# RHA2132_headstage.net
KiCad netlist of a schematic drawn in EAGLE
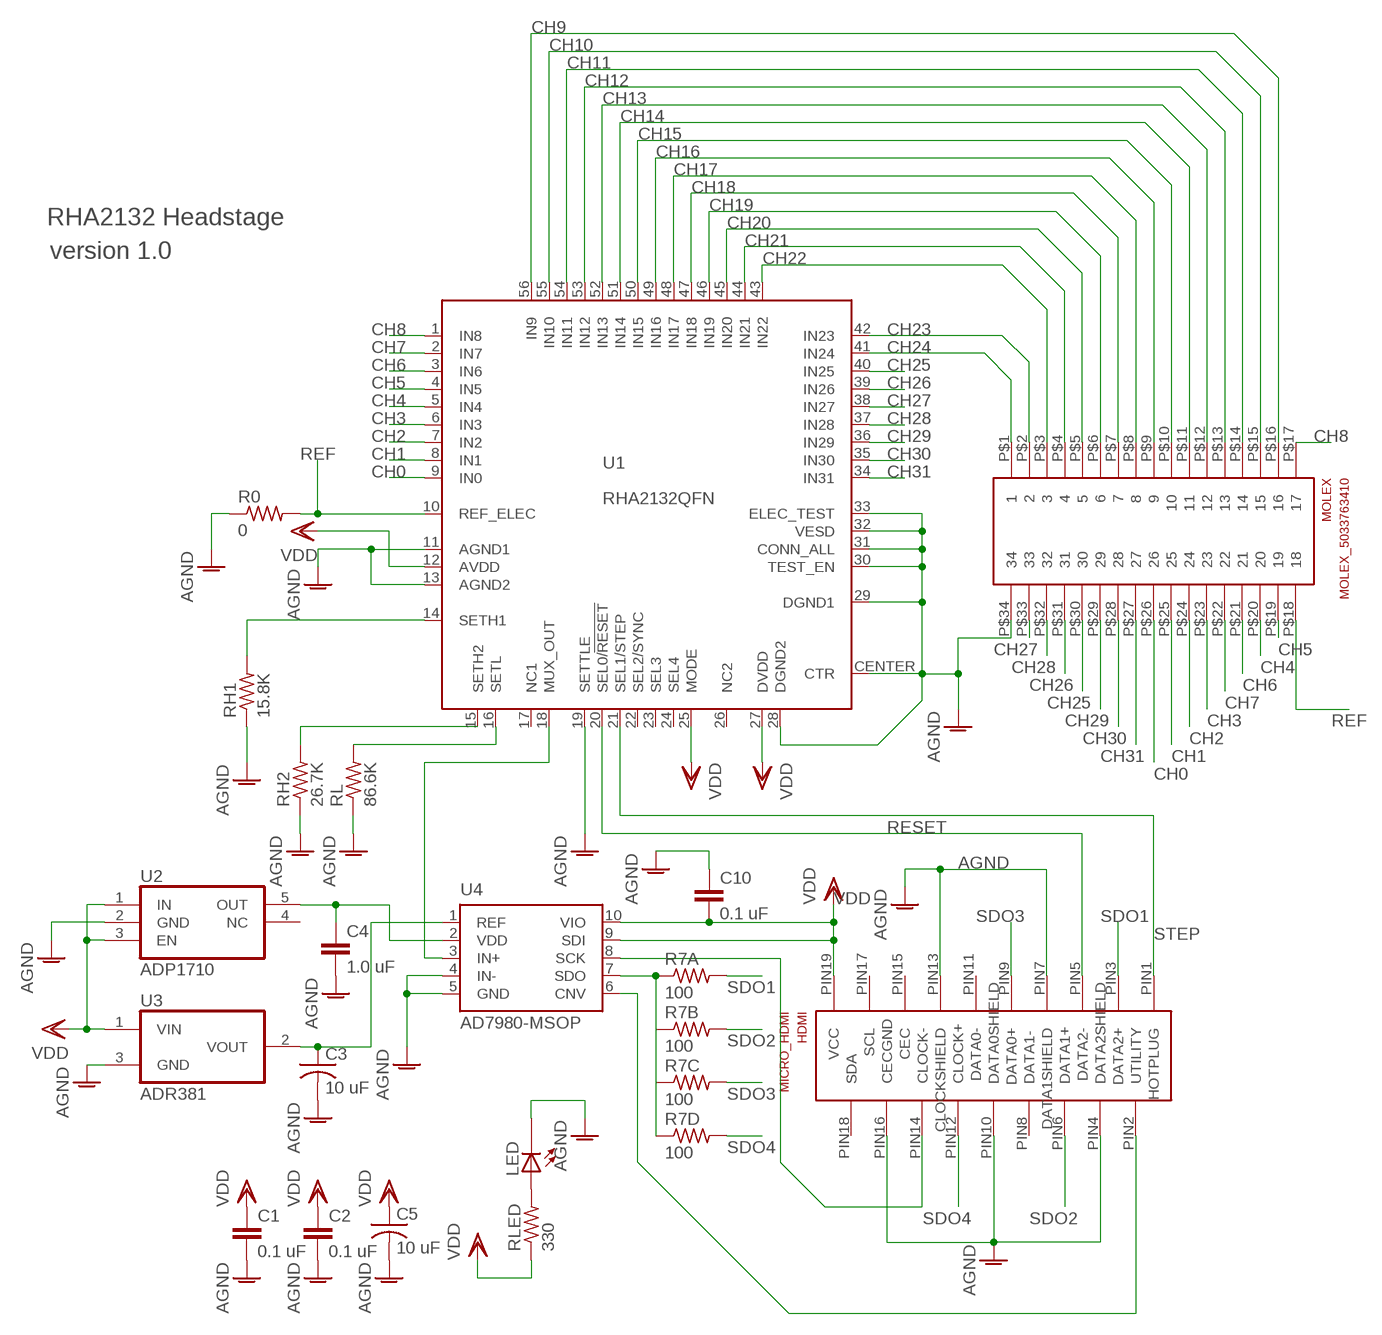
[diagram p0: schematic, sheet 1]

(export (version "E")
  (design (tool "Eeschema 10.0.6"))
  (components
    (comp (ref "C1")
      (value "0.1 uF")
      (footprint "eagle-import:C0402")
      (libsource (lib "eagle-import") (part "C-EUC0402"))
    )
    (comp (ref "C2")
      (value "0.1 uF")
      (footprint "eagle-import:C0402")
      (libsource (lib "eagle-import") (part "C-EUC0402"))
    )
    (comp (ref "C3")
      (value "10 uF")
      (footprint "eagle-import:C0603")
      (libsource (lib "eagle-import") (part "C-USC0603"))
    )
    (comp (ref "C4")
      (value "1.0 uF")
      (footprint "eagle-import:C0402")
      (libsource (lib "eagle-import") (part "C-EUC0402"))
    )
    (comp (ref "C5")
      (value "10 uF")
      (footprint "eagle-import:C0603")
      (libsource (lib "eagle-import") (part "C-USC0603"))
    )
    (comp (ref "C10")
      (value "0.1 uF")
      (footprint "eagle-import:C0402")
      (libsource (lib "eagle-import") (part "C-EUC0402"))
    )
    (comp (ref "HDMI")
      (value "MICRO_HDMI")
      (footprint "eagle-import:MICRO_HDMI")
      (libsource (lib "eagle-import") (part "MICRO_HDMI"))
    )
    (comp (ref "LED")
      (value "LUXEON_REBEL")
      (footprint "eagle-import:LUXEON_REBEL")
      (libsource (lib "eagle-import") (part "LUXEON_REBEL"))
    )
    (comp (ref "MOLEX")
      (value "MOLEX_5033763410")
      (footprint "eagle-import:MOLEX_5033763410")
      (libsource (lib "eagle-import") (part "MOLEX_5033763410"))
    )
    (comp (ref "R0")
      (value "0")
      (footprint "eagle-import:R0603")
      (libsource (lib "eagle-import") (part "R-US_R0603"))
    )
    (comp (ref "R7A")
      (value "100")
      (footprint "eagle-import:R0402")
      (libsource (lib "eagle-import") (part "R-US_R0402"))
    )
    (comp (ref "R7B")
      (value "100")
      (footprint "eagle-import:R0402")
      (libsource (lib "eagle-import") (part "R-US_R0402"))
    )
    (comp (ref "R7C")
      (value "100")
      (footprint "eagle-import:R0402")
      (libsource (lib "eagle-import") (part "R-US_R0402"))
    )
    (comp (ref "R7D")
      (value "100")
      (footprint "eagle-import:R0402")
      (libsource (lib "eagle-import") (part "R-US_R0402"))
    )
    (comp (ref "RH1")
      (value "15.8K")
      (footprint "eagle-import:R0402")
      (libsource (lib "eagle-import") (part "R-US_R0402"))
    )
    (comp (ref "RH2")
      (value "26.7K")
      (footprint "eagle-import:R0402")
      (libsource (lib "eagle-import") (part "R-US_R0402"))
    )
    (comp (ref "RL")
      (value "86.6K")
      (footprint "eagle-import:R0402")
      (libsource (lib "eagle-import") (part "R-US_R0402"))
    )
    (comp (ref "RLED")
      (value "330")
      (footprint "eagle-import:R0402")
      (libsource (lib "eagle-import") (part "R-US_R0402"))
    )
    (comp (ref "U1")
      (value "RHA2132QFN")
      (footprint "eagle-import:QFN56_8_X_8")
      (libsource (lib "eagle-import") (part "RHA2132QFN"))
    )
    (comp (ref "U2")
      (value "ADP1710")
      (footprint "eagle-import:TSOT-23-5")
      (libsource (lib "eagle-import") (part "ADP1710"))
    )
    (comp (ref "U3")
      (value "ADR381")
      (footprint "eagle-import:SOT23")
      (libsource (lib "eagle-import") (part "ADR381"))
    )
    (comp (ref "U4")
      (value "AD7980-MSOP")
      (footprint "eagle-import:MSOP-10")
      (libsource (lib "eagle-import") (part "AD7980-MSOP"))
    )
  )
  (nets
    (net (code "1") (name "/CH0") (class "Default")
      (node (ref "MOLEX") (pin "P$26") (pinfunction "26_P$26") (pintype "bidirectional"))
      (node (ref "U1") (pin "9") (pinfunction "IN0_9") (pintype "input"))
    )
    (net (code "2") (name "/CH1") (class "Default")
      (node (ref "MOLEX") (pin "P$25") (pinfunction "25_P$25") (pintype "bidirectional"))
      (node (ref "U1") (pin "8") (pinfunction "IN1_8") (pintype "input"))
    )
    (net (code "3") (name "/CH2") (class "Default")
      (node (ref "MOLEX") (pin "P$24") (pinfunction "24_P$24") (pintype "bidirectional"))
      (node (ref "U1") (pin "7") (pinfunction "IN2_7") (pintype "input"))
    )
    (net (code "4") (name "/CH3") (class "Default")
      (node (ref "MOLEX") (pin "P$23") (pinfunction "23_P$23") (pintype "bidirectional"))
      (node (ref "U1") (pin "6") (pinfunction "IN3_6") (pintype "input"))
    )
    (net (code "5") (name "/CH4") (class "Default")
      (node (ref "MOLEX") (pin "P$20") (pinfunction "20_P$20") (pintype "bidirectional"))
      (node (ref "U1") (pin "5") (pinfunction "IN4_5") (pintype "input"))
    )
    (net (code "6") (name "/CH5") (class "Default")
      (node (ref "MOLEX") (pin "P$19") (pinfunction "19_P$19") (pintype "bidirectional"))
      (node (ref "U1") (pin "4") (pinfunction "IN5_4") (pintype "input"))
    )
    (net (code "7") (name "/CH6") (class "Default")
      (node (ref "MOLEX") (pin "P$21") (pinfunction "21_P$21") (pintype "bidirectional"))
      (node (ref "U1") (pin "3") (pinfunction "IN6_3") (pintype "input"))
    )
    (net (code "8") (name "/CH7") (class "Default")
      (node (ref "MOLEX") (pin "P$22") (pinfunction "22_P$22") (pintype "bidirectional"))
      (node (ref "U1") (pin "2") (pinfunction "IN7_2") (pintype "input"))
    )
    (net (code "9") (name "/CH8") (class "Default")
      (node (ref "MOLEX") (pin "P$17") (pinfunction "17_P$17") (pintype "bidirectional"))
      (node (ref "U1") (pin "1") (pinfunction "IN8_1") (pintype "input"))
    )
    (net (code "10") (name "/CH9") (class "Default")
      (node (ref "MOLEX") (pin "P$16") (pinfunction "16_P$16") (pintype "bidirectional"))
      (node (ref "U1") (pin "56") (pinfunction "IN9_56") (pintype "input"))
    )
    (net (code "11") (name "/CH10") (class "Default")
      (node (ref "MOLEX") (pin "P$15") (pinfunction "15_P$15") (pintype "bidirectional"))
      (node (ref "U1") (pin "55") (pinfunction "IN10_55") (pintype "input"))
    )
    (net (code "12") (name "/CH11") (class "Default")
      (node (ref "MOLEX") (pin "P$14") (pinfunction "14_P$14") (pintype "bidirectional"))
      (node (ref "U1") (pin "54") (pinfunction "IN11_54") (pintype "input"))
    )
    (net (code "13") (name "/CH12") (class "Default")
      (node (ref "MOLEX") (pin "P$13") (pinfunction "13_P$13") (pintype "bidirectional"))
      (node (ref "U1") (pin "53") (pinfunction "IN12_53") (pintype "input"))
    )
    (net (code "14") (name "/CH13") (class "Default")
      (node (ref "MOLEX") (pin "P$12") (pinfunction "12_P$12") (pintype "bidirectional"))
      (node (ref "U1") (pin "52") (pinfunction "IN13_52") (pintype "input"))
    )
    (net (code "15") (name "/CH14") (class "Default")
      (node (ref "MOLEX") (pin "P$11") (pinfunction "11_P$11") (pintype "bidirectional"))
      (node (ref "U1") (pin "51") (pinfunction "IN14_51") (pintype "input"))
    )
    (net (code "16") (name "/CH15") (class "Default")
      (node (ref "MOLEX") (pin "P$10") (pinfunction "10_P$10") (pintype "bidirectional"))
      (node (ref "U1") (pin "50") (pinfunction "IN15_50") (pintype "input"))
    )
    (net (code "17") (name "/CH16") (class "Default")
      (node (ref "MOLEX") (pin "P$9") (pinfunction "9_P$9") (pintype "bidirectional"))
      (node (ref "U1") (pin "49") (pinfunction "IN16_49") (pintype "input"))
    )
    (net (code "18") (name "/CH17") (class "Default")
      (node (ref "MOLEX") (pin "P$8") (pinfunction "8_P$8") (pintype "bidirectional"))
      (node (ref "U1") (pin "48") (pinfunction "IN17_48") (pintype "input"))
    )
    (net (code "19") (name "/CH18") (class "Default")
      (node (ref "MOLEX") (pin "P$7") (pinfunction "7_P$7") (pintype "bidirectional"))
      (node (ref "U1") (pin "47") (pinfunction "IN18_47") (pintype "input"))
    )
    (net (code "20") (name "/CH19") (class "Default")
      (node (ref "MOLEX") (pin "P$6") (pinfunction "6_P$6") (pintype "bidirectional"))
      (node (ref "U1") (pin "46") (pinfunction "IN19_46") (pintype "input"))
    )
    (net (code "21") (name "/CH20") (class "Default")
      (node (ref "MOLEX") (pin "P$5") (pinfunction "5_P$5") (pintype "bidirectional"))
      (node (ref "U1") (pin "45") (pinfunction "IN20_45") (pintype "input"))
    )
    (net (code "22") (name "/CH21") (class "Default")
      (node (ref "MOLEX") (pin "P$4") (pinfunction "4_P$4") (pintype "bidirectional"))
      (node (ref "U1") (pin "44") (pinfunction "IN21_44") (pintype "input"))
    )
    (net (code "23") (name "/CH22") (class "Default")
      (node (ref "MOLEX") (pin "P$3") (pinfunction "3_P$3") (pintype "bidirectional"))
      (node (ref "U1") (pin "43") (pinfunction "IN22_43") (pintype "input"))
    )
    (net (code "24") (name "/CH23") (class "Default")
      (node (ref "MOLEX") (pin "P$2") (pinfunction "2_P$2") (pintype "bidirectional"))
      (node (ref "U1") (pin "42") (pinfunction "IN23_42") (pintype "input"))
    )
    (net (code "25") (name "/CH24") (class "Default")
      (node (ref "MOLEX") (pin "P$1") (pinfunction "1_P$1") (pintype "bidirectional"))
      (node (ref "U1") (pin "41") (pinfunction "IN24_41") (pintype "input"))
    )
    (net (code "26") (name "/CH25") (class "Default")
      (node (ref "MOLEX") (pin "P$30") (pinfunction "30_P$30") (pintype "bidirectional"))
      (node (ref "U1") (pin "40") (pinfunction "IN25_40") (pintype "input"))
    )
    (net (code "27") (name "/CH26") (class "Default")
      (node (ref "MOLEX") (pin "P$31") (pinfunction "31_P$31") (pintype "bidirectional"))
      (node (ref "U1") (pin "39") (pinfunction "IN26_39") (pintype "input"))
    )
    (net (code "28") (name "/CH27") (class "Default")
      (node (ref "MOLEX") (pin "P$33") (pinfunction "33_P$33") (pintype "bidirectional"))
      (node (ref "U1") (pin "38") (pinfunction "IN27_38") (pintype "input"))
    )
    (net (code "29") (name "/CH28") (class "Default")
      (node (ref "MOLEX") (pin "P$32") (pinfunction "32_P$32") (pintype "bidirectional"))
      (node (ref "U1") (pin "37") (pinfunction "IN28_37") (pintype "input"))
    )
    (net (code "30") (name "/CH29") (class "Default")
      (node (ref "MOLEX") (pin "P$29") (pinfunction "29_P$29") (pintype "bidirectional"))
      (node (ref "U1") (pin "36") (pinfunction "IN29_36") (pintype "input"))
    )
    (net (code "31") (name "/CH30") (class "Default")
      (node (ref "MOLEX") (pin "P$28") (pinfunction "28_P$28") (pintype "bidirectional"))
      (node (ref "U1") (pin "35") (pinfunction "IN30_35") (pintype "input"))
    )
    (net (code "32") (name "/CH31") (class "Default")
      (node (ref "MOLEX") (pin "P$27") (pinfunction "27_P$27") (pintype "bidirectional"))
      (node (ref "U1") (pin "34") (pinfunction "IN31_34") (pintype "input"))
    )
    (net (code "33") (name "/REF") (class "Default")
      (node (ref "MOLEX") (pin "P$18") (pinfunction "18_P$18") (pintype "bidirectional"))
      (node (ref "R0") (pin "2") (pinfunction "2_2") (pintype "passive"))
      (node (ref "U1") (pin "10") (pinfunction "REF_ELEC_10") (pintype "input"))
    )
    (net (code "34") (name "/RESET") (class "Default")
      (node (ref "HDMI") (pin "PIN5") (pinfunction "DATA2-_PIN5") (pintype "bidirectional"))
      (node (ref "U1") (pin "20") (pinfunction "SEL0/~{RESET}_20") (pintype "input"))
    )
    (net (code "35") (name "/SDO1") (class "Default")
      (node (ref "HDMI") (pin "PIN3") (pinfunction "DATA2+_PIN3") (pintype "bidirectional"))
      (node (ref "R7A") (pin "2") (pinfunction "2_2") (pintype "passive"))
    )
    (net (code "36") (name "/SDO2") (class "Default")
      (node (ref "HDMI") (pin "PIN6") (pinfunction "DATA1+_PIN6") (pintype "bidirectional"))
      (node (ref "R7B") (pin "2") (pinfunction "2_2") (pintype "passive"))
    )
    (net (code "37") (name "/SDO3") (class "Default")
      (node (ref "HDMI") (pin "PIN9") (pinfunction "DATA0+_PIN9") (pintype "bidirectional"))
      (node (ref "R7C") (pin "2") (pinfunction "2_2") (pintype "passive"))
    )
    (net (code "38") (name "/SDO4") (class "Default")
      (node (ref "HDMI") (pin "PIN12") (pinfunction "CLOCK+_PIN12") (pintype "bidirectional"))
      (node (ref "R7D") (pin "2") (pinfunction "2_2") (pintype "passive"))
    )
    (net (code "39") (name "/STEP") (class "Default")
      (node (ref "HDMI") (pin "PIN1") (pinfunction "HOTPLUG_PIN1") (pintype "bidirectional"))
      (node (ref "U1") (pin "21") (pinfunction "SEL1/STEP_21") (pintype "input"))
    )
    (net (code "40") (name "AGND") (class "Default")
      (node (ref "C1") (pin "2") (pinfunction "2_2") (pintype "passive"))
      (node (ref "C10") (pin "1") (pinfunction "1_1") (pintype "passive"))
      (node (ref "C2") (pin "2") (pinfunction "2_2") (pintype "passive"))
      (node (ref "C3") (pin "2") (pinfunction "2_2") (pintype "passive"))
      (node (ref "C4") (pin "2") (pinfunction "2_2") (pintype "passive"))
      (node (ref "C5") (pin "2") (pinfunction "2_2") (pintype "passive"))
      (node (ref "HDMI") (pin "PIN10") (pinfunction "DATA0SHIELD_PIN10") (pintype "bidirectional"))
      (node (ref "HDMI") (pin "PIN13") (pinfunction "CLOCKSHIELD_PIN13") (pintype "bidirectional"))
      (node (ref "HDMI") (pin "PIN16") (pinfunction "CECGND_PIN16") (pintype "bidirectional"))
      (node (ref "HDMI") (pin "PIN4") (pinfunction "DATA2SHIELD_PIN4") (pintype "bidirectional"))
      (node (ref "HDMI") (pin "PIN7") (pinfunction "DATA1SHIELD_PIN7") (pintype "bidirectional"))
      (node (ref "LED") (pin "C") (pinfunction "C_C") (pintype "passive"))
      (node (ref "MOLEX") (pin "P$34") (pinfunction "34_P$34") (pintype "bidirectional"))
      (node (ref "R0") (pin "1") (pinfunction "1_1") (pintype "passive"))
      (node (ref "RH1") (pin "1") (pinfunction "1_1") (pintype "passive"))
      (node (ref "RH2") (pin "1") (pinfunction "1_1") (pintype "passive"))
      (node (ref "RL") (pin "1") (pinfunction "1_1") (pintype "passive"))
      (node (ref "U1") (pin "11") (pinfunction "AGND1_11") (pintype "power_in"))
      (node (ref "U1") (pin "13") (pinfunction "AGND2_13") (pintype "power_in"))
      (node (ref "U1") (pin "19") (pinfunction "SETTLE_19") (pintype "input"))
      (node (ref "U1") (pin "28") (pinfunction "DGND2_28") (pintype "power_in"))
      (node (ref "U1") (pin "29") (pinfunction "DGND1_29") (pintype "power_in"))
      (node (ref "U1") (pin "30") (pinfunction "TEST_EN_30") (pintype "input"))
      (node (ref "U1") (pin "31") (pinfunction "CONN_ALL_31") (pintype "input"))
      (node (ref "U1") (pin "32") (pinfunction "VESD_32") (pintype "power_in"))
      (node (ref "U1") (pin "33") (pinfunction "ELEC_TEST_33") (pintype "input"))
      (node (ref "U1") (pin "CENTER") (pinfunction "CTR_CENTER") (pintype "power_in"))
      (node (ref "U2") (pin "2") (pinfunction "GND_2") (pintype "power_in"))
      (node (ref "U3") (pin "3") (pinfunction "GND_3") (pintype "power_in"))
      (node (ref "U4") (pin "4") (pinfunction "IN-_4") (pintype "input"))
      (node (ref "U4") (pin "5") (pinfunction "GND_5") (pintype "power_in"))
    )
    (net (code "41") (name "Net-(HDMI-CLOCK-)") (class "Default")
      (node (ref "HDMI") (pin "PIN14") (pinfunction "CLOCK-_PIN14") (pintype "bidirectional"))
      (node (ref "U4") (pin "8") (pinfunction "SCK_8") (pintype "input"))
    )
    (net (code "42") (name "Net-(HDMI-UTILITY)") (class "Default")
      (node (ref "HDMI") (pin "PIN2") (pinfunction "UTILITY_PIN2") (pintype "bidirectional"))
      (node (ref "U4") (pin "6") (pinfunction "CNV_6") (pintype "input"))
    )
    (net (code "43") (name "Net-(LED-PadA)") (class "Default")
      (node (ref "LED") (pin "A") (pinfunction "A_A") (pintype "passive"))
      (node (ref "RLED") (pin "2") (pinfunction "2_2") (pintype "passive"))
    )
    (net (code "44") (name "Net-(U1-MUX_OUT)") (class "Default")
      (node (ref "U1") (pin "18") (pinfunction "MUX_OUT_18") (pintype "tri_state"))
      (node (ref "U4") (pin "3") (pinfunction "IN+_3") (pintype "input"))
    )
    (net (code "45") (name "Net-(U1-SETH1)") (class "Default")
      (node (ref "RH1") (pin "2") (pinfunction "2_2") (pintype "passive"))
      (node (ref "U1") (pin "14") (pinfunction "SETH1_14") (pintype "passive"))
    )
    (net (code "46") (name "Net-(U1-SETH2)") (class "Default")
      (node (ref "RH2") (pin "2") (pinfunction "2_2") (pintype "passive"))
      (node (ref "U1") (pin "15") (pinfunction "SETH2_15") (pintype "passive"))
    )
    (net (code "47") (name "Net-(U1-SETL)") (class "Default")
      (node (ref "RL") (pin "2") (pinfunction "2_2") (pintype "passive"))
      (node (ref "U1") (pin "16") (pinfunction "SETL_16") (pintype "passive"))
    )
    (net (code "48") (name "Net-(U2-OUT)") (class "Default")
      (node (ref "C4") (pin "1") (pinfunction "1_1") (pintype "passive"))
      (node (ref "U2") (pin "5") (pinfunction "OUT_5") (pintype "power_in"))
      (node (ref "U4") (pin "2") (pinfunction "VDD_2") (pintype "power_in"))
    )
    (net (code "49") (name "Net-(U3-VOUT)") (class "Default")
      (node (ref "C3") (pin "1") (pinfunction "1_1") (pintype "passive"))
      (node (ref "U3") (pin "2") (pinfunction "VOUT_2") (pintype "power_in"))
      (node (ref "U4") (pin "1") (pinfunction "REF_1") (pintype "input"))
    )
    (net (code "50") (name "Net-(U4-SDO)") (class "Default")
      (node (ref "R7A") (pin "1") (pinfunction "1_1") (pintype "passive"))
      (node (ref "R7D") (pin "1") (pinfunction "1_1") (pintype "passive"))
      (node (ref "U4") (pin "7") (pinfunction "SDO_7") (pintype "output"))
    )
    (net (code "51") (name "VDD") (class "Default")
      (node (ref "C1") (pin "1") (pinfunction "1_1") (pintype "passive"))
      (node (ref "C10") (pin "2") (pinfunction "2_2") (pintype "passive"))
      (node (ref "C2") (pin "1") (pinfunction "1_1") (pintype "passive"))
      (node (ref "C5") (pin "1") (pinfunction "1_1") (pintype "passive"))
      (node (ref "HDMI") (pin "PIN19") (pinfunction "VCC_PIN19") (pintype "bidirectional"))
      (node (ref "RLED") (pin "1") (pinfunction "1_1") (pintype "passive"))
      (node (ref "U1") (pin "12") (pinfunction "AVDD_12") (pintype "power_in"))
      (node (ref "U1") (pin "25") (pinfunction "MODE_25") (pintype "input"))
      (node (ref "U1") (pin "27") (pinfunction "DVDD_27") (pintype "power_in"))
      (node (ref "U2") (pin "1") (pinfunction "IN_1") (pintype "power_in"))
      (node (ref "U2") (pin "3") (pinfunction "EN_3") (pintype "input"))
      (node (ref "U3") (pin "1") (pinfunction "VIN_1") (pintype "power_in"))
      (node (ref "U4") (pin "10") (pinfunction "VIO_10") (pintype "power_in"))
      (node (ref "U4") (pin "9") (pinfunction "SDI_9") (pintype "input"))
    )
    (net (code "52") (name "unconnected-(HDMI-CEC-PadPIN15)") (class "Default")
      (node (ref "HDMI") (pin "PIN15") (pinfunction "CEC_PIN15") (pintype "bidirectional"))
    )
    (net (code "53") (name "unconnected-(HDMI-DATA0--PadPIN11)") (class "Default")
      (node (ref "HDMI") (pin "PIN11") (pinfunction "DATA0-_PIN11") (pintype "bidirectional"))
    )
    (net (code "54") (name "unconnected-(HDMI-DATA1--PadPIN8)") (class "Default")
      (node (ref "HDMI") (pin "PIN8") (pinfunction "DATA1-_PIN8") (pintype "bidirectional"))
    )
    (net (code "55") (name "unconnected-(HDMI-SCL-PadPIN17)") (class "Default")
      (node (ref "HDMI") (pin "PIN17") (pinfunction "SCL_PIN17") (pintype "bidirectional"))
    )
    (net (code "56") (name "unconnected-(HDMI-SDA-PadPIN18)") (class "Default")
      (node (ref "HDMI") (pin "PIN18") (pinfunction "SDA_PIN18") (pintype "bidirectional"))
    )
    (net (code "57") (name "unconnected-(LEDA-A-PadA@1)") (class "Default")
      (node (ref "LED") (pin "A@1") (pinfunction "A_A@1") (pintype "passive"))
    )
    (net (code "58") (name "unconnected-(LEDA-C-PadC@1)") (class "Default")
      (node (ref "LED") (pin "C@1") (pinfunction "C_C@1") (pintype "passive"))
    )
    (net (code "59") (name "unconnected-(R7B-Pad1)") (class "Default")
      (node (ref "R7B") (pin "1") (pinfunction "1_1") (pintype "passive"))
    )
    (net (code "60") (name "unconnected-(R7C-Pad1)") (class "Default")
      (node (ref "R7C") (pin "1") (pinfunction "1_1") (pintype "passive"))
    )
    (net (code "61") (name "unconnected-(U1-NC1-Pad17)") (class "Default")
      (node (ref "U1") (pin "17") (pinfunction "NC1_17") (pintype "no_connect"))
    )
    (net (code "62") (name "unconnected-(U1-NC2-Pad26)") (class "Default")
      (node (ref "U1") (pin "26") (pinfunction "NC2_26") (pintype "no_connect"))
    )
    (net (code "63") (name "unconnected-(U1-SEL2{slash}SYNC-Pad22)") (class "Default")
      (node (ref "U1") (pin "22") (pinfunction "SEL2/SYNC_22") (pintype "bidirectional"))
    )
    (net (code "64") (name "unconnected-(U1-SEL3-Pad23)") (class "Default")
      (node (ref "U1") (pin "23") (pinfunction "SEL3_23") (pintype "bidirectional"))
    )
    (net (code "65") (name "unconnected-(U1-SEL4-Pad24)") (class "Default")
      (node (ref "U1") (pin "24") (pinfunction "SEL4_24") (pintype "input"))
    )
    (net (code "66") (name "unconnected-(U2-NC-Pad4)") (class "Default")
      (node (ref "U2") (pin "4") (pinfunction "NC_4") (pintype "no_connect"))
    )
  )
)
